# SPI.net
KiCad netlist of a schematic drawn in Altium Designer
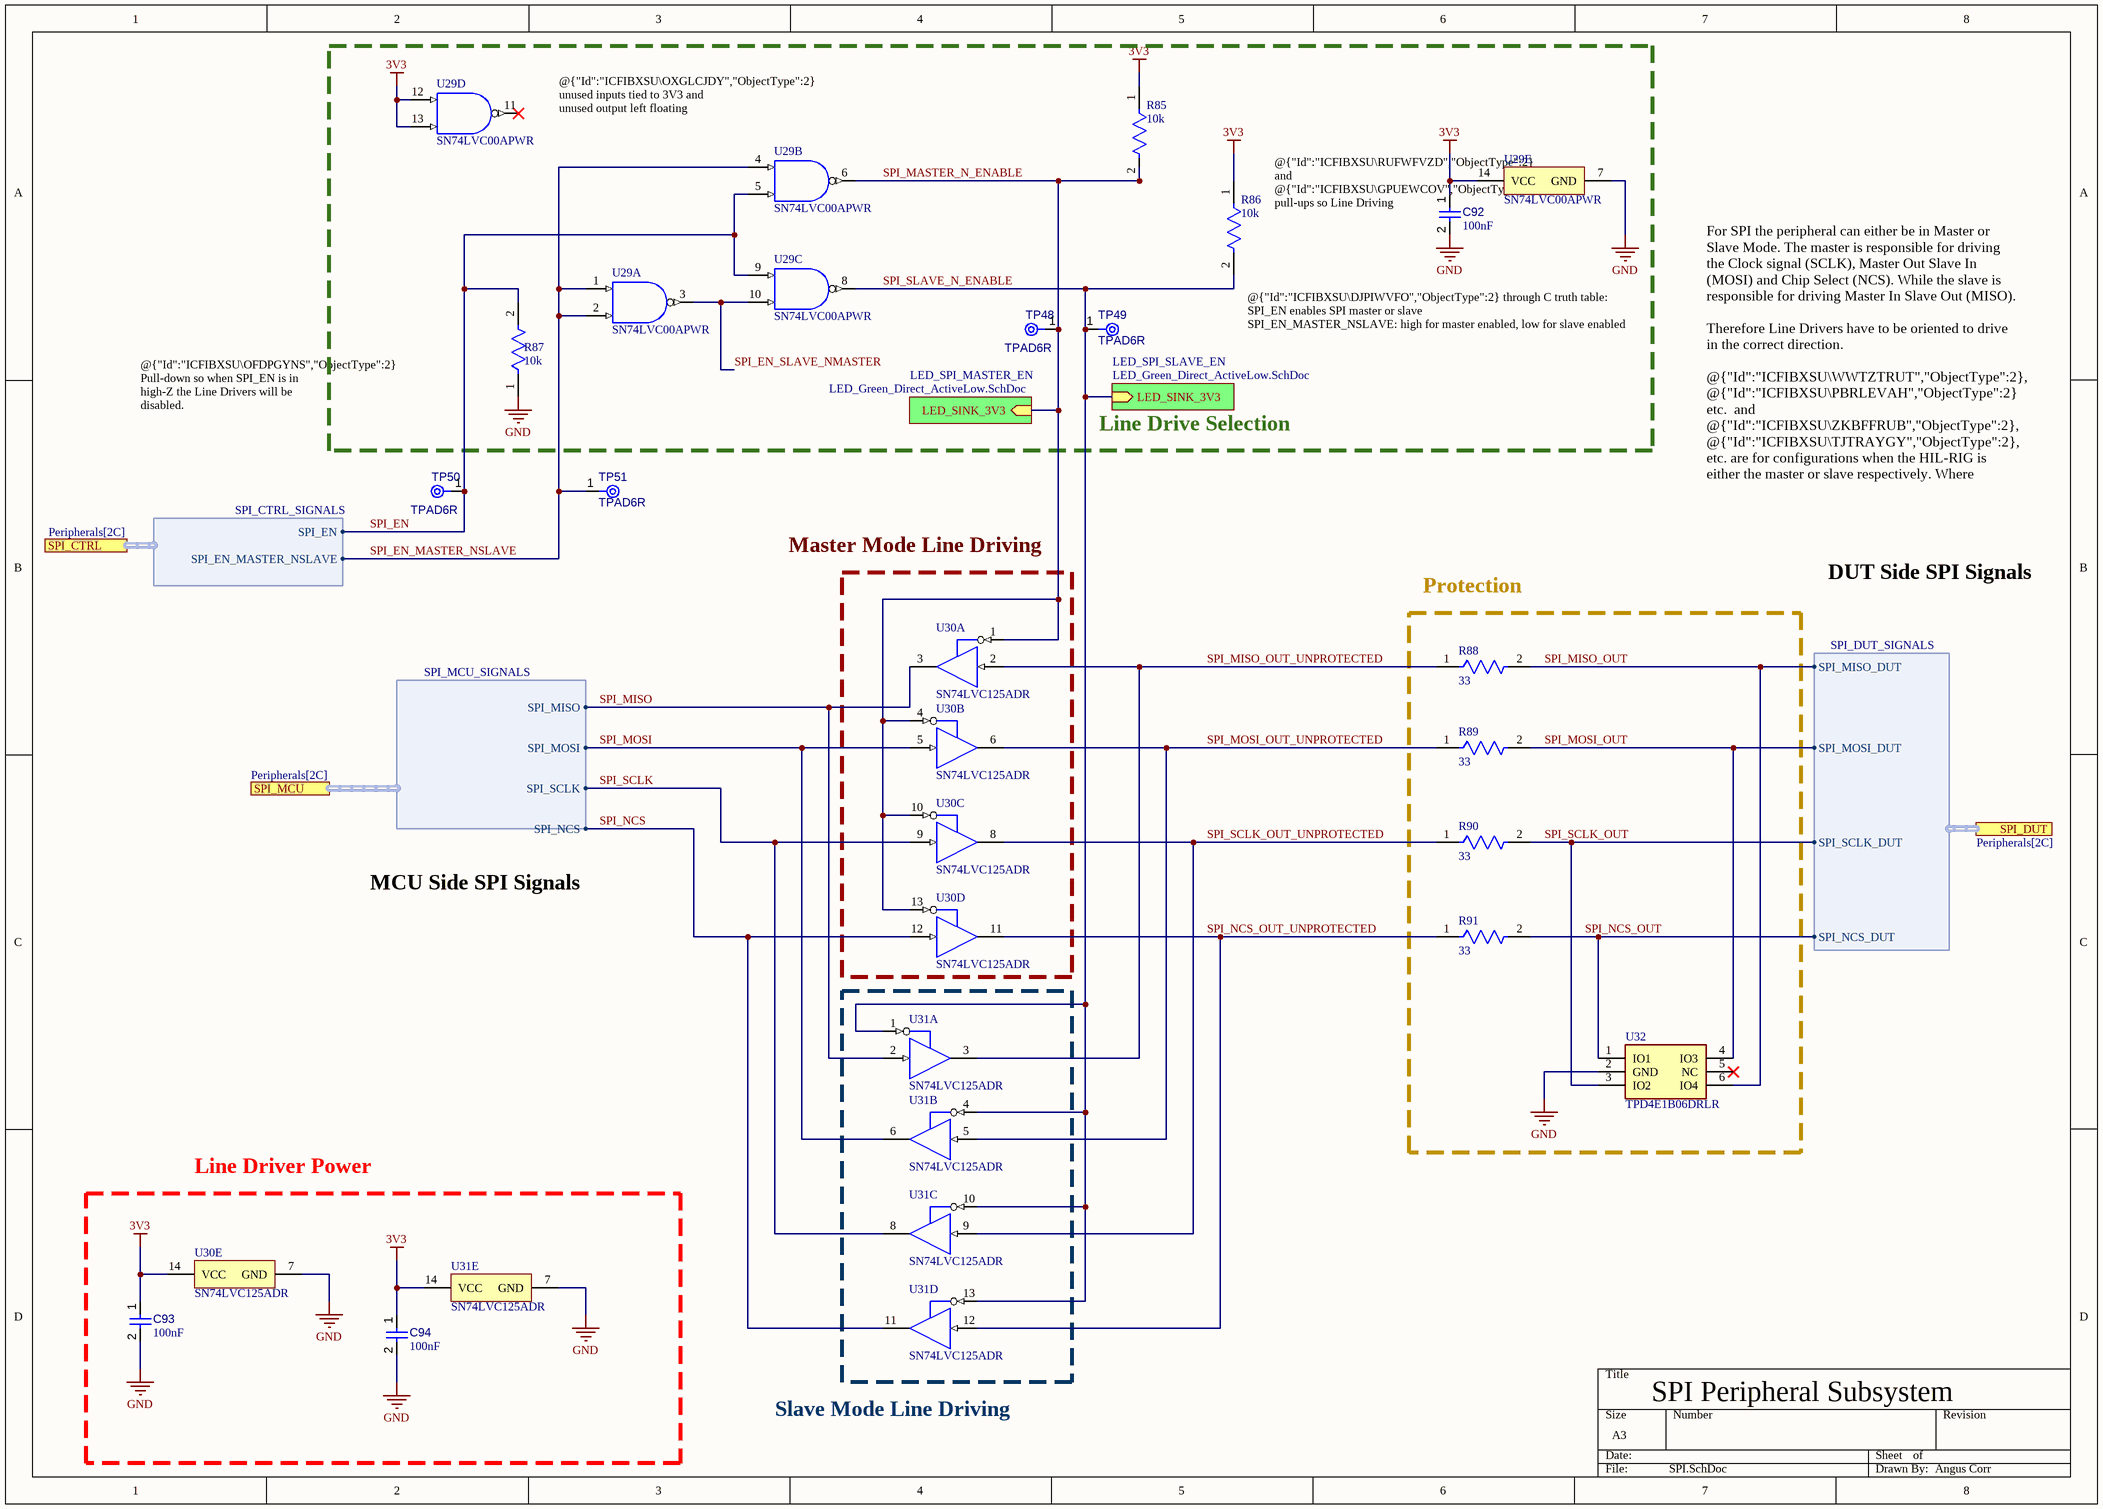
[diagram p0:  SPI.SchDoc]

(export (version "E")
  (design (tool "Eeschema 10.0.6"))
  (components
    (comp (ref "C92")
      (value "100nF")
      (footprint "CAPC1608X90X40NL10T20")
      (description "Chip Capacitor, 100 nF, +/- 10%, 50 V, 0603 (1608 Metric)")
      (fields (field (name "TOLERANCE") "10%") (field (name "Comment") "Capacitor 100 nF +/-10% 50 V 0603"))
      (libsource (lib "HIL RIG FYP") (part "CAP-NP-2"))
    )
    (comp (ref "C93")
      (value "100nF")
      (footprint "CAPC1608X90X40NL10T20")
      (description "Chip Capacitor, 100 nF, +/- 10%, 50 V, 0603 (1608 Metric)")
      (fields (field (name "TOLERANCE") "10%") (field (name "Comment") "Capacitor 100 nF +/-10% 50 V 0603"))
      (libsource (lib "HIL RIG FYP") (part "CAP-NP-2"))
    )
    (comp (ref "C94")
      (value "100nF")
      (footprint "CAPC1608X90X40NL10T20")
      (description "Chip Capacitor, 100 nF, +/- 10%, 50 V, 0603 (1608 Metric)")
      (fields (field (name "TOLERANCE") "10%") (field (name "Comment") "Capacitor 100 nF +/-10% 50 V 0603"))
      (libsource (lib "HIL RIG FYP") (part "CAP-NP-2"))
    )
    (comp (ref "R85")
      (value "10k")
      (footprint "FP-RT0603-IPC_C")
      (description "Res Thin Film 0603 10K Ohm 0.1% 1/10W ¦25ppm/¦C SMD Paper T/R")
      (fields (field (name "TOLERANCE") "0.1%") (field (name "Comment") "RT0603BRD0710KL"))
      (libsource (lib "HIL RIG FYP") (part "1029c3af85768c4190bb7ad29bc67b5"))
    )
    (comp (ref "R86")
      (value "10k")
      (footprint "FP-RT0603-IPC_C")
      (description "Res Thin Film 0603 10K Ohm 0.1% 1/10W ¦25ppm/¦C SMD Paper T/R")
      (fields (field (name "TOLERANCE") "0.1%") (field (name "Comment") "RT0603BRD0710KL"))
      (libsource (lib "HIL RIG FYP") (part "1029c3af85768c4190bb7ad29bc67b5"))
    )
    (comp (ref "R87")
      (value "10k")
      (footprint "FP-RT0603-IPC_C")
      (description "Res Thin Film 0603 10K Ohm 0.1% 1/10W ¦25ppm/¦C SMD Paper T/R")
      (fields (field (name "TOLERANCE") "0.1%") (field (name "Comment") "RT0603BRD0710KL"))
      (libsource (lib "HIL RIG FYP") (part "1029c3af85768c4190bb7ad29bc67b5"))
    )
    (comp (ref "R88")
      (value "33")
      (footprint "FP-AC0603-IPC_C")
      (description "Res Thick Film 0603 33 Ohm 1% 0.1W(1/10W) ±100ppm/C Pad SMD T/R Automotive AEC-Q200")
      (fields (field (name "TOLERANCE") "1%") (field (name "Comment") "AC0603FR-0733RL"))
      (libsource (lib "HIL RIG FYP") (part "1029c3af85768c4190bb7ad29bc67b5"))
    )
    (comp (ref "R89")
      (value "33")
      (footprint "FP-AC0603-IPC_C")
      (description "Res Thick Film 0603 33 Ohm 1% 0.1W(1/10W) ±100ppm/C Pad SMD T/R Automotive AEC-Q200")
      (fields (field (name "TOLERANCE") "1%") (field (name "Comment") "AC0603FR-0733RL"))
      (libsource (lib "HIL RIG FYP") (part "1029c3af85768c4190bb7ad29bc67b5"))
    )
    (comp (ref "R90")
      (value "33")
      (footprint "FP-AC0603-IPC_C")
      (description "Res Thick Film 0603 33 Ohm 1% 0.1W(1/10W) ±100ppm/C Pad SMD T/R Automotive AEC-Q200")
      (fields (field (name "TOLERANCE") "1%") (field (name "Comment") "AC0603FR-0733RL"))
      (libsource (lib "HIL RIG FYP") (part "1029c3af85768c4190bb7ad29bc67b5"))
    )
    (comp (ref "R91")
      (value "33")
      (footprint "FP-AC0603-IPC_C")
      (description "Res Thick Film 0603 33 Ohm 1% 0.1W(1/10W) ±100ppm/C Pad SMD T/R Automotive AEC-Q200")
      (fields (field (name "TOLERANCE") "1%") (field (name "Comment") "AC0603FR-0733RL"))
      (libsource (lib "HIL RIG FYP") (part "1029c3af85768c4190bb7ad29bc67b5"))
    )
    (comp (ref "TP48")
      (value "TPAD6R")
      (footprint "TP06R")
      (description "0.6mm round")
      (libsource (lib "HIL RIG FYP") (part "CMP-001-0001-4"))
    )
    (comp (ref "TP49")
      (value "TPAD6R")
      (footprint "TP06R")
      (description "0.6mm round")
      (libsource (lib "HIL RIG FYP") (part "CMP-001-0001-4"))
    )
    (comp (ref "TP50")
      (value "TPAD6R")
      (footprint "TP06R")
      (description "0.6mm round")
      (libsource (lib "HIL RIG FYP") (part "CMP-001-0001-4"))
    )
    (comp (ref "TP51")
      (value "TPAD6R")
      (footprint "TP06R")
      (description "0.6mm round")
      (libsource (lib "HIL RIG FYP") (part "CMP-001-0001-4"))
    )
    (comp (ref "U29")
      (value "SN74LVC00APWR")
      (footprint "FP-PW0014A-IPC_B")
      (description "4.1NS@ 3.3V, 50PF 1 2 4 4 1.65V 3.6V 24MA Nand Gate Lvc 24MA TSSOP-14 , 1.2MM")
      (libsource (lib "HIL RIG FYP") (part "TI-NAND-4-2IN-14_G"))
    )
    (comp (ref "U30")
      (value "SN74LVC125ADR")
      (footprint "FP-D0014A-MFG")
      (description "24mA 24mA 1.65V~3.6V -40℃~+125℃ Tri-State SOIC-14 Buffer/Driver/Transceiver ROHS")
      (libsource (lib "") (part "TI-SN74LVC125A-Q1-D0014A-14_1"))
    )
    (comp (ref "U31")
      (value "SN74LVC125ADR")
      (footprint "FP-D0014A-MFG")
      (description "24mA 24mA 1.65V~3.6V -40℃~+125℃ Tri-State SOIC-14 Buffer/Driver/Transceiver ROHS")
      (libsource (lib "HIL RIG FYP") (part "TI-SN74LVC125A-Q1-D0014A-14"))
    )
    (comp (ref "U32")
      (value "TPD4E1B06DRLR")
      (footprint "SOTFL50P160X60-6N")
      (description "Bidirectional Quad-Channel High-Speed ESD Protection Device")
      (fields (field (name "MOUSER PART NUMBER") "595-TPD4E1B06DRLR"))
      (libsource (lib "HIL RIG FYP") (part "TPD4E1B06DRLR"))
    )
  )
  (nets
    (net (code "4") (name "/SPI_EN") (class "Default")
      (node (ref "R87") (pin "2") (pinfunction "2_2") (pintype "passive"))
      (node (ref "TP50") (pin "1") (pinfunction "TP_1") (pintype "passive"))
      (node (ref "U29") (pin "5") (pinfunction "2B_5") (pintype "input"))
      (node (ref "U29") (pin "9") (pinfunction "3A_9") (pintype "input"))
    )
    (net (code "5") (name "/SPI_EN_MASTER_NSLAVE") (class "Default")
      (node (ref "TP51") (pin "1") (pinfunction "TP_1") (pintype "passive"))
      (node (ref "U29") (pin "1") (pinfunction "1A_1") (pintype "input"))
      (node (ref "U29") (pin "2") (pinfunction "1B_2") (pintype "input"))
      (node (ref "U29") (pin "4") (pinfunction "2A_4") (pintype "input"))
    )
    (net (code "6") (name "/SPI_EN_SLAVE_NMASTER") (class "Default")
      (node (ref "U29") (pin "10") (pinfunction "3B_10") (pintype "input"))
      (node (ref "U29") (pin "3") (pinfunction "1Y_3") (pintype "output"))
    )
    (net (code "7") (name "/SPI_MASTER_N_ENABLE") (class "Default")
      (node (ref "R85") (pin "2") (pinfunction "2_2") (pintype "passive"))
      (node (ref "TP48") (pin "1") (pinfunction "TP_1") (pintype "passive"))
      (node (ref "U29") (pin "6") (pinfunction "2Y_6") (pintype "output"))
      (node (ref "U30") (pin "1") (pinfunction "1~{OE}_1") (pintype "input"))
      (node (ref "U30") (pin "10") (pinfunction "3~{OE}_10") (pintype "input"))
      (node (ref "U30") (pin "13") (pinfunction "4~{OE}_13") (pintype "input"))
      (node (ref "U30") (pin "4") (pinfunction "2~{OE}_4") (pintype "input"))
    )
    (net (code "8") (name "/SPI_MISO") (class "Default")
      (node (ref "U30") (pin "3") (pinfunction "1Y_3") (pintype "tri_state"))
      (node (ref "U31") (pin "2") (pinfunction "1A_2") (pintype "input"))
    )
    (net (code "9") (name "/SPI_MISO_OUT") (class "Default")
      (node (ref "R88") (pin "2") (pinfunction "2_2") (pintype "passive"))
      (node (ref "U32") (pin "6") (pinfunction "IO4_6") (pintype "passive"))
    )
    (net (code "10") (name "/SPI_MISO_OUT_UNPROTECTED") (class "Default")
      (node (ref "R88") (pin "1") (pinfunction "1_1") (pintype "passive"))
      (node (ref "U30") (pin "2") (pinfunction "1A_2") (pintype "input"))
      (node (ref "U31") (pin "3") (pinfunction "1Y_3") (pintype "tri_state"))
    )
    (net (code "11") (name "/SPI_MOSI") (class "Default")
      (node (ref "U30") (pin "5") (pinfunction "2A_5") (pintype "input"))
      (node (ref "U31") (pin "6") (pinfunction "2Y_6") (pintype "tri_state"))
    )
    (net (code "12") (name "/SPI_MOSI_OUT") (class "Default")
      (node (ref "R89") (pin "2") (pinfunction "2_2") (pintype "passive"))
      (node (ref "U32") (pin "4") (pinfunction "IO3_4") (pintype "passive"))
    )
    (net (code "13") (name "/SPI_MOSI_OUT_UNPROTECTED") (class "Default")
      (node (ref "R89") (pin "1") (pinfunction "1_1") (pintype "passive"))
      (node (ref "U30") (pin "6") (pinfunction "2Y_6") (pintype "tri_state"))
      (node (ref "U31") (pin "5") (pinfunction "2A_5") (pintype "input"))
    )
    (net (code "14") (name "/SPI_NCS") (class "Default")
      (node (ref "U30") (pin "12") (pinfunction "4A_12") (pintype "input"))
      (node (ref "U31") (pin "11") (pinfunction "4Y_11") (pintype "tri_state"))
    )
    (net (code "15") (name "/SPI_NCS_OUT") (class "Default")
      (node (ref "R91") (pin "2") (pinfunction "2_2") (pintype "passive"))
      (node (ref "U32") (pin "1") (pinfunction "IO1_1") (pintype "passive"))
    )
    (net (code "16") (name "/SPI_NCS_OUT_UNPROTECTED") (class "Default")
      (node (ref "R91") (pin "1") (pinfunction "1_1") (pintype "passive"))
      (node (ref "U30") (pin "11") (pinfunction "4Y_11") (pintype "tri_state"))
      (node (ref "U31") (pin "12") (pinfunction "4A_12") (pintype "input"))
    )
    (net (code "17") (name "/SPI_SCLK") (class "Default")
      (node (ref "U30") (pin "9") (pinfunction "3A_9") (pintype "input"))
      (node (ref "U31") (pin "8") (pinfunction "3Y_8") (pintype "tri_state"))
    )
    (net (code "18") (name "/SPI_SCLK_OUT") (class "Default")
      (node (ref "R90") (pin "2") (pinfunction "2_2") (pintype "passive"))
      (node (ref "U32") (pin "3") (pinfunction "IO2_3") (pintype "passive"))
    )
    (net (code "19") (name "/SPI_SCLK_OUT_UNPROTECTED") (class "Default")
      (node (ref "R90") (pin "1") (pinfunction "1_1") (pintype "passive"))
      (node (ref "U30") (pin "8") (pinfunction "3Y_8") (pintype "tri_state"))
      (node (ref "U31") (pin "9") (pinfunction "3A_9") (pintype "input"))
    )
    (net (code "20") (name "/SPI_SLAVE_N_ENABLE") (class "Default")
      (node (ref "R86") (pin "2") (pinfunction "2_2") (pintype "passive"))
      (node (ref "TP49") (pin "1") (pinfunction "TP_1") (pintype "passive"))
      (node (ref "U29") (pin "8") (pinfunction "3Y_8") (pintype "output"))
      (node (ref "U31") (pin "1") (pinfunction "1~{OE}_1") (pintype "input"))
      (node (ref "U31") (pin "10") (pinfunction "3~{OE}_10") (pintype "input"))
      (node (ref "U31") (pin "13") (pinfunction "4~{OE}_13") (pintype "input"))
      (node (ref "U31") (pin "4") (pinfunction "2~{OE}_4") (pintype "input"))
    )
    (net (code "24") (name "3V3") (class "Default")
      (node (ref "C92") (pin "1") (pinfunction "1_1") (pintype "passive"))
      (node (ref "C93") (pin "1") (pinfunction "1_1") (pintype "passive"))
      (node (ref "C94") (pin "1") (pinfunction "1_1") (pintype "passive"))
      (node (ref "R85") (pin "1") (pinfunction "1_1") (pintype "passive"))
      (node (ref "R86") (pin "1") (pinfunction "1_1") (pintype "passive"))
      (node (ref "U29") (pin "12") (pinfunction "4A_12") (pintype "input"))
      (node (ref "U29") (pin "13") (pinfunction "4B_13") (pintype "input"))
      (node (ref "U29") (pin "14") (pinfunction "VCC_14") (pintype "power_in"))
      (node (ref "U30") (pin "14") (pinfunction "VCC_14") (pintype "power_in"))
      (node (ref "U31") (pin "14") (pinfunction "VCC_14") (pintype "power_in"))
    )
    (net (code "25") (name "GND") (class "Default")
      (node (ref "C92") (pin "2") (pinfunction "2_2") (pintype "passive"))
      (node (ref "C93") (pin "2") (pinfunction "2_2") (pintype "passive"))
      (node (ref "C94") (pin "2") (pinfunction "2_2") (pintype "passive"))
      (node (ref "R87") (pin "1") (pinfunction "1_1") (pintype "passive"))
      (node (ref "U29") (pin "7") (pinfunction "GND_7") (pintype "power_in"))
      (node (ref "U30") (pin "7") (pinfunction "GND_7") (pintype "power_in"))
      (node (ref "U31") (pin "7") (pinfunction "GND_7") (pintype "power_in"))
      (node (ref "U32") (pin "2") (pinfunction "GND_2") (pintype "passive"))
    )
    (net (code "26") (name "unconnected-(U29D-4Y-Pad11)") (class "Default")
      (node (ref "U29") (pin "11") (pinfunction "4Y_11") (pintype "output+no_connect"))
    )
    (net (code "27") (name "unconnected-(U32-NC-Pad5)") (class "Default")
      (node (ref "U32") (pin "5") (pinfunction "NC_5") (pintype "passive+no_connect"))
    )
  )
)
